# Sheet2.net
KiCad netlist of a schematic drawn in Altium Designer
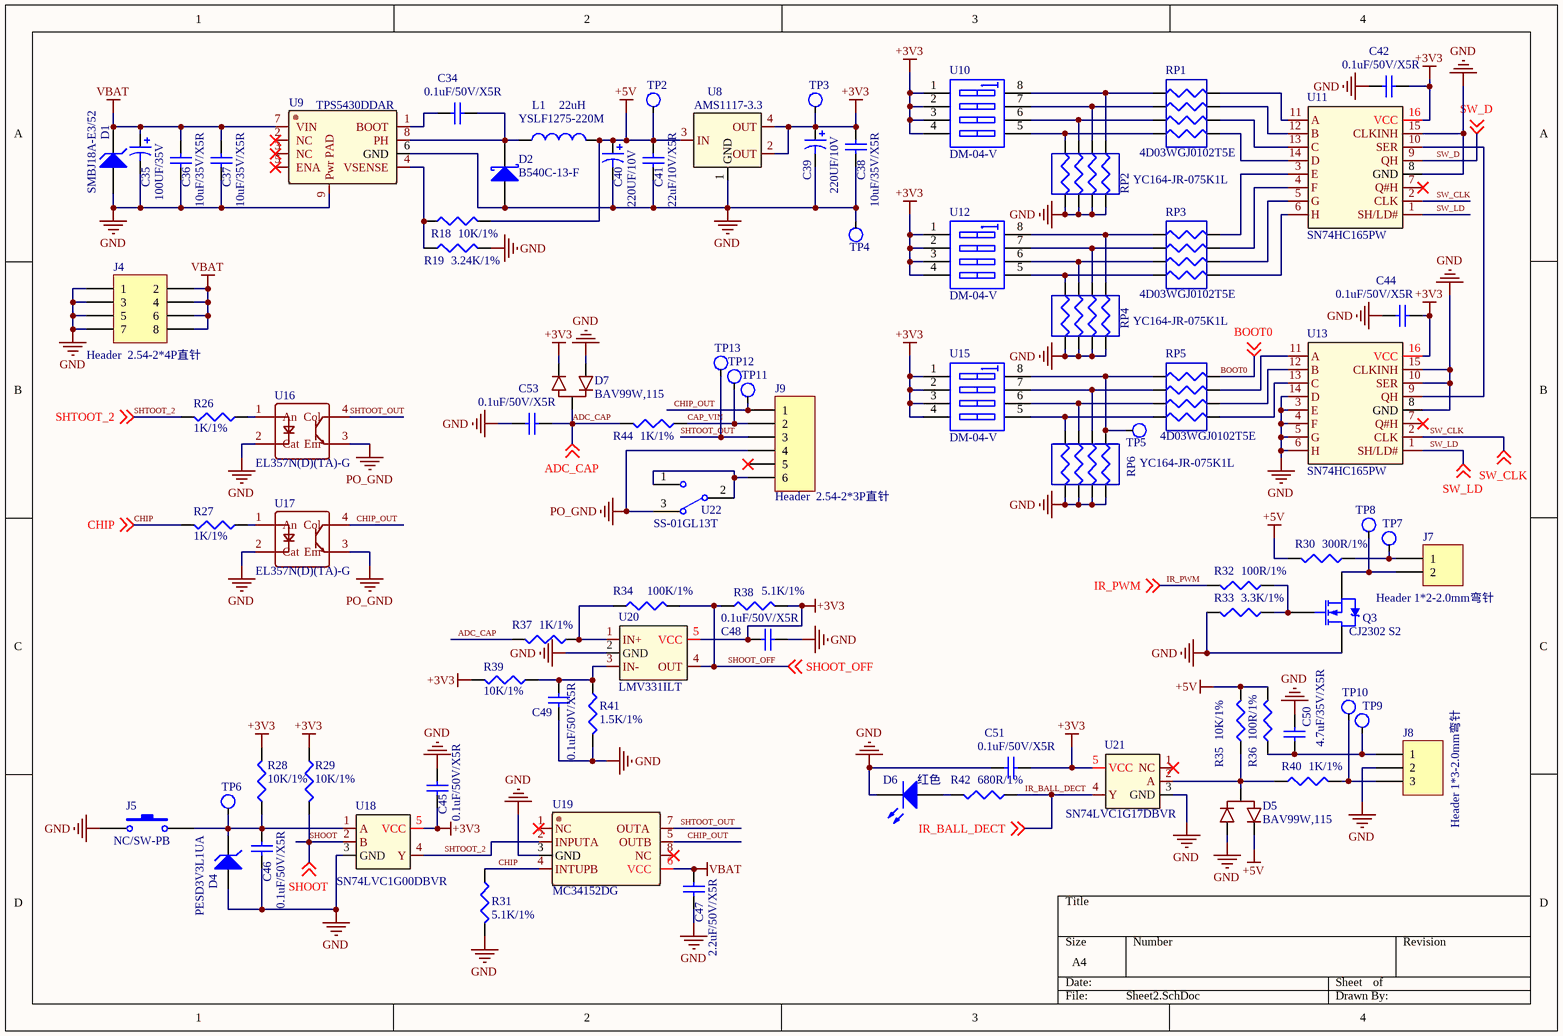
[diagram p0: Sheet2.SchDoc]

(export (version "E")
  (design (tool "Eeschema 10.0.6"))
  (components
    (comp (ref "C34")
      (value "0.1uF/50V/X5R")
      (footprint "C0603")
      (description "Capacitor (Semiconductor SIM Model)")
      (fields (field (name "PUBLISHER") "Altium Limited"))
      (libsource (lib "Miscellaneous Devices") (part "Cap Semi"))
    )
    (comp (ref "C35")
      (value "100UF/35V")
      (footprint "SMD_5X5.4")
      (description "Polarized Capacitor (Radial)")
      (fields (field (name "PUBLISHER") "Altium Limited"))
      (libsource (lib "Miscellaneous Devices") (part "Cap Pol1"))
    )
    (comp (ref "C36")
      (value "10uF/35V/X5R")
      (footprint "C1206")
      (description "Capacitor (Semiconductor SIM Model)")
      (fields (field (name "PUBLISHER") "Altium Limited"))
      (libsource (lib "Miscellaneous Devices") (part "Cap Semi"))
    )
    (comp (ref "C37")
      (value "10uF/35V/X5R")
      (footprint "C1206")
      (description "Capacitor (Semiconductor SIM Model)")
      (fields (field (name "PUBLISHER") "Altium Limited"))
      (libsource (lib "Miscellaneous Devices") (part "Cap Semi"))
    )
    (comp (ref "C38")
      (value "10uF/35V/X5R")
      (footprint "C0805")
      (description "Capacitor (Semiconductor SIM Model)")
      (fields (field (name "PUBLISHER") "Altium Limited"))
      (libsource (lib "Miscellaneous Devices") (part "Cap Semi"))
    )
    (comp (ref "C39")
      (value "220UF/10V")
      (footprint "SMD_5X5.4")
      (description "Polarized Capacitor (Radial)")
      (fields (field (name "PUBLISHER") "Altium Limited"))
      (libsource (lib "Miscellaneous Devices") (part "Cap Pol1"))
    )
    (comp (ref "C40")
      (value "220UF/10V")
      (footprint "SMD_5X5.4")
      (description "Polarized Capacitor (Radial)")
      (fields (field (name "PUBLISHER") "Altium Limited"))
      (libsource (lib "Miscellaneous Devices") (part "Cap Pol1"))
    )
    (comp (ref "C41")
      (value "22uF/10V/X5R")
      (footprint "C0805")
      (description "Capacitor (Semiconductor SIM Model)")
      (fields (field (name "PUBLISHER") "Altium Limited"))
      (libsource (lib "Miscellaneous Devices") (part "Cap Semi"))
    )
    (comp (ref "C42")
      (value "0.1uF/50V/X5R")
      (footprint "C0603")
      (description "Capacitor (Semiconductor SIM Model)")
      (fields (field (name "PUBLISHER") "Altium Limited"))
      (libsource (lib "Miscellaneous Devices") (part "Cap Semi"))
    )
    (comp (ref "C44")
      (value "0.1uF/50V/X5R")
      (footprint "C0603")
      (description "Capacitor (Semiconductor SIM Model)")
      (fields (field (name "PUBLISHER") "Altium Limited"))
      (libsource (lib "Miscellaneous Devices") (part "Cap Semi"))
    )
    (comp (ref "C45")
      (value "0.1uF/50V/X5R")
      (footprint "C0603")
      (description "Capacitor (Semiconductor SIM Model)")
      (fields (field (name "PUBLISHER") "Altium Limited"))
      (libsource (lib "Miscellaneous Devices") (part "Cap Semi"))
    )
    (comp (ref "C46")
      (value "0.1uF/50V/X5R")
      (footprint "C0603")
      (description "Capacitor (Semiconductor SIM Model)")
      (fields (field (name "PUBLISHER") "Altium Limited"))
      (libsource (lib "Miscellaneous Devices") (part "Cap Semi"))
    )
    (comp (ref "C47")
      (value "2.2uF/50V/X5R")
      (footprint "C0603")
      (description "Capacitor (Semiconductor SIM Model)")
      (fields (field (name "PUBLISHER") "Altium Limited"))
      (libsource (lib "Miscellaneous Devices") (part "Cap Semi"))
    )
    (comp (ref "C48")
      (value "0.1uF/50V/X5R")
      (footprint "C0603")
      (description "Capacitor (Semiconductor SIM Model)")
      (fields (field (name "PUBLISHER") "Altium Limited"))
      (libsource (lib "Miscellaneous Devices") (part "Cap Semi"))
    )
    (comp (ref "C49")
      (value "0.1uF/50V/X5R")
      (footprint "C0603")
      (description "Capacitor (Semiconductor SIM Model)")
      (fields (field (name "PUBLISHER") "Altium Limited"))
      (libsource (lib "Miscellaneous Devices") (part "Cap Semi"))
    )
    (comp (ref "C50")
      (value "4.7uF/35V/X5R")
      (footprint "C0603")
      (description "Capacitor (Semiconductor SIM Model)")
      (fields (field (name "PUBLISHER") "Altium Limited"))
      (libsource (lib "Miscellaneous Devices") (part "Cap Semi"))
    )
    (comp (ref "C51")
      (value "0.1uF/50V/X5R")
      (footprint "C0603")
      (description "Capacitor (Semiconductor SIM Model)")
      (fields (field (name "PUBLISHER") "Altium Limited"))
      (libsource (lib "Miscellaneous Devices") (part "Cap Semi"))
    )
    (comp (ref "C53")
      (value "0.1uF/50V/X5R")
      (footprint "C0603")
      (description "Capacitor (Semiconductor SIM Model)")
      (fields (field (name "PUBLISHER") "Altium Limited"))
      (libsource (lib "Miscellaneous Devices") (part "Cap Semi"))
    )
    (comp (ref "D1")
      (value "SMBJ18A-E3/52")
      (footprint "SMB")
      (description "Zener Diode")
      (fields (field (name "PUBLISHER") "Altium Limited"))
      (libsource (lib "Miscellaneous Devices") (part "D Zener"))
    )
    (comp (ref "D2")
      (value "B540C-13-F")
      (footprint "SMC")
      (description "Schottky Diode")
      (fields (field (name "PUBLISHER") "Altium Limited"))
      (libsource (lib "Miscellaneous Devices") (part "D Schottky"))
    )
    (comp (ref "D4")
      (value "PESD3V3L1UA")
      (footprint "SOD-323")
      (libsource (lib "Schlib1") (part "PESD3V3L1UA"))
    )
    (comp (ref "D5") (value "BAV99W,115") (libsource (lib "Schlib1") (part "BAV99W,115")))
    (comp (ref "D6")
      (value "红色")
      (footprint "LED0603")
      (description "Typical RED, GREEN, YELLOW, AMBER GaAs LED")
      (fields (field (name "PUBLISHER") "Altium Limited"))
      (libsource (lib "Miscellaneous Devices") (part "LED2"))
    )
    (comp (ref "D7") (value "BAV99W,115") (libsource (lib "Schlib1") (part "BAV99W,115")))
    (comp (ref "J4")
      (value "Header  2.54-2*4P直针")
      (footprint "DIP_2X4_2.54")
      (description "Header, 4-Pin, Dual row")
      (fields (field (name "PUBLISHER") "Altium Limited"))
      (libsource (lib "Miscellaneous Connectors") (part "Header 4X2"))
    )
    (comp (ref "J5")
      (value "NC/SW-PB")
      (footprint "SMD-AJ")
      (description "Switch")
      (fields (field (name "PUBLISHER") "Altium Limited"))
      (libsource (lib "Miscellaneous Devices") (part "SW-PB"))
    )
    (comp (ref "J7")
      (value "Header 1*2-2.0mm弯针")
      (footprint "DIP_1X2_2MM1")
      (description "Header, 2-Pin")
      (fields (field (name "PUBLISHER") "Altium Limited"))
      (libsource (lib "Miscellaneous Connectors") (part "Header 2"))
    )
    (comp (ref "J8")
      (value "Header 1*3-2.0mm弯针")
      (footprint "DIP_1X3_2MM")
      (description "Header, 3-Pin")
      (fields (field (name "PUBLISHER") "Altium Limited"))
      (libsource (lib "Miscellaneous Connectors") (part "Header 3"))
    )
    (comp (ref "J9")
      (value "Header  2.54-2*3P直针")
      (footprint "DIP_2X3_2.54")
      (description "Header, 6-Pin")
      (fields (field (name "PUBLISHER") "Altium Limited"))
      (libsource (lib "Miscellaneous Connectors") (part "Header 6"))
    )
    (comp (ref "L1")
      (value "YSLF1275-220M")
      (footprint "SMD_12.5X12.")
      (description "Inductor")
      (fields (field (name "ALTIUM_VALUE") "22uH") (field (name "PUBLISHER") "Altium Limited"))
      (libsource (lib "Miscellaneous Devices") (part "Inductor"))
    )
    (comp (ref "Q3")
      (value "CJ2302 S2")
      (footprint "SOT-23")
      (description "N-Channel Power MOSFET")
      (fields (field (name "PUBLISHER") "Altium Limited"))
      (libsource (lib "Miscellaneous Devices") (part "NMOS-2"))
    )
    (comp (ref "R18")
      (value "10K/1%")
      (footprint "R0603")
      (description "Resistor")
      (fields (field (name "PUBLISHER") "Altium Limited"))
      (libsource (lib "Miscellaneous Devices") (part "Res3"))
    )
    (comp (ref "R19")
      (value "3.24K/1%")
      (footprint "R0603")
      (description "Resistor")
      (fields (field (name "PUBLISHER") "Altium Limited"))
      (libsource (lib "Miscellaneous Devices") (part "Res3"))
    )
    (comp (ref "R26")
      (value "1K/1%")
      (footprint "R0603")
      (description "Resistor")
      (fields (field (name "PUBLISHER") "Altium Limited"))
      (libsource (lib "Miscellaneous Devices") (part "Res3"))
    )
    (comp (ref "R27")
      (value "1K/1%")
      (footprint "R0603")
      (description "Resistor")
      (fields (field (name "PUBLISHER") "Altium Limited"))
      (libsource (lib "Miscellaneous Devices") (part "Res3"))
    )
    (comp (ref "R28")
      (value "10K/1%")
      (footprint "R0603")
      (description "Resistor")
      (fields (field (name "PUBLISHER") "Altium Limited"))
      (libsource (lib "Miscellaneous Devices") (part "Res3"))
    )
    (comp (ref "R29")
      (value "10K/1%")
      (footprint "R0603")
      (description "Resistor")
      (fields (field (name "PUBLISHER") "Altium Limited"))
      (libsource (lib "Miscellaneous Devices") (part "Res3"))
    )
    (comp (ref "R30")
      (value "300R/1%")
      (footprint "R0603")
      (description "Resistor")
      (fields (field (name "PUBLISHER") "Altium Limited"))
      (libsource (lib "Miscellaneous Devices") (part "Res3"))
    )
    (comp (ref "R31")
      (value "5.1K/1%")
      (footprint "R0603")
      (description "Resistor")
      (fields (field (name "PUBLISHER") "Altium Limited"))
      (libsource (lib "Miscellaneous Devices") (part "Res3"))
    )
    (comp (ref "R32")
      (value "100R/1%")
      (footprint "R0603")
      (description "Resistor")
      (fields (field (name "PUBLISHER") "Altium Limited"))
      (libsource (lib "Miscellaneous Devices") (part "Res3"))
    )
    (comp (ref "R33")
      (value "3.3K/1%")
      (footprint "R0603")
      (description "Resistor")
      (fields (field (name "PUBLISHER") "Altium Limited"))
      (libsource (lib "Miscellaneous Devices") (part "Res3"))
    )
    (comp (ref "R34")
      (value "100K/1%")
      (footprint "R0603")
      (description "Resistor")
      (fields (field (name "PUBLISHER") "Altium Limited"))
      (libsource (lib "Miscellaneous Devices") (part "Res3"))
    )
    (comp (ref "R35")
      (value "10K/1%")
      (footprint "R0603")
      (description "Resistor")
      (fields (field (name "PUBLISHER") "Altium Limited"))
      (libsource (lib "Miscellaneous Devices") (part "Res3"))
    )
    (comp (ref "R36")
      (value "100R/1%")
      (footprint "R0603")
      (description "Resistor")
      (fields (field (name "PUBLISHER") "Altium Limited"))
      (libsource (lib "Miscellaneous Devices") (part "Res3"))
    )
    (comp (ref "R37")
      (value "1K/1%")
      (footprint "R0603")
      (description "Resistor")
      (fields (field (name "PUBLISHER") "Altium Limited"))
      (libsource (lib "Miscellaneous Devices") (part "Res3"))
    )
    (comp (ref "R38")
      (value "5.1K/1%")
      (footprint "R0603")
      (description "Resistor")
      (fields (field (name "PUBLISHER") "Altium Limited"))
      (libsource (lib "Miscellaneous Devices") (part "Res3"))
    )
    (comp (ref "R39")
      (value "10K/1%")
      (footprint "R0603")
      (description "Resistor")
      (fields (field (name "PUBLISHER") "Altium Limited"))
      (libsource (lib "Miscellaneous Devices") (part "Res3"))
    )
    (comp (ref "R40")
      (value "1K/1%")
      (footprint "R0603")
      (description "Resistor")
      (fields (field (name "PUBLISHER") "Altium Limited"))
      (libsource (lib "Miscellaneous Devices") (part "Res3"))
    )
    (comp (ref "R41")
      (value "1.5K/1%")
      (footprint "R0603")
      (description "Resistor")
      (fields (field (name "PUBLISHER") "Altium Limited"))
      (libsource (lib "Miscellaneous Devices") (part "Res3"))
    )
    (comp (ref "R42")
      (value "680R/1%")
      (footprint "R0603")
      (description "Resistor")
      (fields (field (name "PUBLISHER") "Altium Limited"))
      (libsource (lib "Miscellaneous Devices") (part "Res3"))
    )
    (comp (ref "R44")
      (value "1K/1%")
      (footprint "R0603")
      (description "Resistor")
      (fields (field (name "PUBLISHER") "Altium Limited"))
      (libsource (lib "Miscellaneous Devices") (part "Res3"))
    )
    (comp (ref "RP1") (value "4D03WGJ0102T5E") (footprint "RP-1206") (libsource (lib "Schlib1") (part "RP")))
    (comp (ref "RP2") (value "YC164-JR-075K1L") (footprint "RP-1206") (libsource (lib "Schlib1") (part "RP")))
    (comp (ref "RP3") (value "4D03WGJ0102T5E") (footprint "RP-1206") (libsource (lib "Schlib1") (part "RP")))
    (comp (ref "RP4") (value "YC164-JR-075K1L") (footprint "RP-1206") (libsource (lib "Schlib1") (part "RP")))
    (comp (ref "RP5") (value "4D03WGJ0102T5E") (footprint "RP-1206") (libsource (lib "Schlib1") (part "RP")))
    (comp (ref "RP6") (value "YC164-JR-075K1L") (footprint "RP-1206") (libsource (lib "Schlib1") (part "RP")))
    (comp (ref "TP2") (value "TP") (footprint "TP") (libsource (lib "Schlib1") (part "TP")))
    (comp (ref "TP3") (value "TP") (footprint "TP") (libsource (lib "Schlib1") (part "TP")))
    (comp (ref "TP4") (value "TP") (footprint "TP") (libsource (lib "Schlib1") (part "TP")))
    (comp (ref "TP5") (value "TP") (footprint "TP") (libsource (lib "Schlib1") (part "TP")))
    (comp (ref "TP6") (value "TP") (footprint "TP") (libsource (lib "Schlib1") (part "TP")))
    (comp (ref "TP7") (value "TP") (footprint "TP") (libsource (lib "Schlib1") (part "TP")))
    (comp (ref "TP8") (value "TP") (footprint "TP") (libsource (lib "Schlib1") (part "TP")))
    (comp (ref "TP9") (value "TP") (footprint "TP") (libsource (lib "Schlib1") (part "TP")))
    (comp (ref "TP10") (value "TP") (footprint "TP") (libsource (lib "Schlib1") (part "TP")))
    (comp (ref "TP11") (value "TP") (footprint "TP") (libsource (lib "Schlib1") (part "TP")))
    (comp (ref "TP12") (value "TP") (footprint "TP") (libsource (lib "Schlib1") (part "TP")))
    (comp (ref "TP13") (value "TP") (footprint "TP") (libsource (lib "Schlib1") (part "TP")))
    (comp (ref "U8")
      (value "AMS1117-3.3")
      (footprint "SOT-223")
      (libsource (lib "Schlib1") (part "AMS1117-3.3"))
    )
    (comp (ref "U9")
      (value "TPS5430DDAR")
      (footprint "SO-8")
      (libsource (lib "Schlib1") (part "TPS5430DDAR"))
    )
    (comp (ref "U10")
      (value "DM-04-V")
      (footprint "SMD_DM04")
      (description "DIP Switch, 4 Position, SPST")
      (fields (field (name "PUBLISHER") "Altium Limited"))
      (libsource (lib "Miscellaneous Devices") (part "SW DIP-4"))
    )
    (comp (ref "U11")
      (value "SN74HC165PW")
      (footprint "TSSOP-16")
      (libsource (lib "Schlib1") (part "SN74HC165PW"))
    )
    (comp (ref "U12")
      (value "DM-04-V")
      (footprint "SMD_DM04")
      (description "DIP Switch, 4 Position, SPST")
      (fields (field (name "PUBLISHER") "Altium Limited"))
      (libsource (lib "Miscellaneous Devices") (part "SW DIP-4"))
    )
    (comp (ref "U13")
      (value "SN74HC165PW")
      (footprint "TSSOP-16")
      (libsource (lib "Schlib1") (part "SN74HC165PW"))
    )
    (comp (ref "U15")
      (value "DM-04-V")
      (footprint "SMD_DM04")
      (description "DIP Switch, 4 Position, SPST")
      (fields (field (name "PUBLISHER") "Altium Limited"))
      (libsource (lib "Miscellaneous Devices") (part "SW DIP-4"))
    )
    (comp (ref "U16")
      (value "EL357N(D)(TA)-G")
      (footprint "SOP-4_P2.54")
      (libsource (lib "Schlib1") (part "EL357N(D)(TA)-G"))
    )
    (comp (ref "U17")
      (value "EL357N(D)(TA)-G")
      (footprint "SOP-4_P2.54")
      (libsource (lib "Schlib1") (part "EL357N(D)(TA)-G"))
    )
    (comp (ref "U18")
      (value "SN74LVC1G00DBVR")
      (footprint "SOT-23-5")
      (libsource (lib "Schlib1") (part "SN74LVC1G00DBVR"))
    )
    (comp (ref "U19") (value "MC34152DG") (footprint "SOIC-8") (libsource (lib "Schlib1") (part "MC34152DG")))
    (comp (ref "U20")
      (value "LMV331ILT")
      (footprint "SOT-23-5")
      (libsource (lib "Schlib1") (part "LMV331IDBVR"))
    )
    (comp (ref "U21")
      (value "SN74LVC1G17DBVR")
      (footprint "SOT-23-5")
      (libsource (lib "Schlib1") (part "SN74LVC1G17DBVR"))
    )
    (comp (ref "U22")
      (value "SS-01GL13T")
      (footprint "SW-6.4X19.8")
      (description "SPDT Subminiature Toggle Switch, Right Angle Mounting, Vertical Actuation")
      (fields (field (name "PUBLISHER") "Altium Limited"))
      (libsource (lib "Miscellaneous Devices") (part "SW-SPDT"))
    )
  )
  (nets
    (net (code "1") (name "+3V3") (class "Default")
      (node (ref "C38") (pin "1") (pinfunction "1_1") (pintype "passive"))
      (node (ref "C39") (pin "1") (pinfunction "1_1") (pintype "passive"))
      (node (ref "C42") (pin "1") (pinfunction "1_1") (pintype "passive"))
      (node (ref "C44") (pin "1") (pinfunction "1_1") (pintype "passive"))
      (node (ref "C45") (pin "1") (pinfunction "1_1") (pintype "passive"))
      (node (ref "C48") (pin "2") (pinfunction "2_2") (pintype "passive"))
      (node (ref "C51") (pin "1") (pinfunction "1_1") (pintype "passive"))
      (node (ref "D7") (pin "2") (pinfunction "2_2") (pintype "passive"))
      (node (ref "R28") (pin "2") (pinfunction "2_2") (pintype "passive"))
      (node (ref "R29") (pin "1") (pinfunction "1_1") (pintype "passive"))
      (node (ref "R38") (pin "2") (pinfunction "2_2") (pintype "passive"))
      (node (ref "R39") (pin "2") (pinfunction "2_2") (pintype "passive"))
      (node (ref "TP3") (pin "1") (pinfunction "1_1") (pintype "passive"))
      (node (ref "U10") (pin "1") (pinfunction "A1_1") (pintype "passive"))
      (node (ref "U10") (pin "2") (pinfunction "A2_2") (pintype "passive"))
      (node (ref "U10") (pin "3") (pinfunction "A3_3") (pintype "passive"))
      (node (ref "U10") (pin "4") (pinfunction "A4_4") (pintype "passive"))
      (node (ref "U11") (pin "16") (pinfunction "VCC_16") (pintype "passive"))
      (node (ref "U12") (pin "1") (pinfunction "A1_1") (pintype "passive"))
      (node (ref "U12") (pin "2") (pinfunction "A2_2") (pintype "passive"))
      (node (ref "U12") (pin "3") (pinfunction "A3_3") (pintype "passive"))
      (node (ref "U12") (pin "4") (pinfunction "A4_4") (pintype "passive"))
      (node (ref "U13") (pin "16") (pinfunction "VCC_16") (pintype "passive"))
      (node (ref "U15") (pin "1") (pinfunction "A1_1") (pintype "passive"))
      (node (ref "U15") (pin "2") (pinfunction "A2_2") (pintype "passive"))
      (node (ref "U15") (pin "3") (pinfunction "A3_3") (pintype "passive"))
      (node (ref "U15") (pin "4") (pinfunction "A4_4") (pintype "passive"))
      (node (ref "U18") (pin "5") (pinfunction "VCC_5") (pintype "passive"))
      (node (ref "U20") (pin "5") (pinfunction "VCC_5") (pintype "passive"))
      (node (ref "U21") (pin "5") (pinfunction "VCC_5") (pintype "passive"))
      (node (ref "U8") (pin "2") (pinfunction "OUT_2") (pintype "passive"))
      (node (ref "U8") (pin "4") (pinfunction "OUT_4") (pintype "passive"))
    )
    (net (code "2") (name "+5V") (class "Default")
      (node (ref "C40") (pin "1") (pinfunction "1_1") (pintype "passive"))
      (node (ref "C41") (pin "1") (pinfunction "1_1") (pintype "passive"))
      (node (ref "D5") (pin "2") (pinfunction "2_2") (pintype "passive"))
      (node (ref "L1") (pin "1") (pinfunction "1_1") (pintype "passive"))
      (node (ref "R18") (pin "2") (pinfunction "2_2") (pintype "passive"))
      (node (ref "R30") (pin "2") (pinfunction "2_2") (pintype "passive"))
      (node (ref "R35") (pin "2") (pinfunction "2_2") (pintype "passive"))
      (node (ref "R36") (pin "2") (pinfunction "2_2") (pintype "passive"))
      (node (ref "TP2") (pin "1") (pinfunction "1_1") (pintype "passive"))
      (node (ref "U8") (pin "3") (pinfunction "IN_3") (pintype "passive"))
    )
    (net (code "3") (name "/CAP_VIN") (class "Default")
      (node (ref "J9") (pin "2") (pinfunction "2_2") (pintype "passive"))
      (node (ref "R44") (pin "1") (pinfunction "1_1") (pintype "passive"))
      (node (ref "TP12") (pin "1") (pinfunction "1_1") (pintype "passive"))
    )
    (net (code "4") (name "/CHIP_OUT") (class "Default")
      (node (ref "J9") (pin "1") (pinfunction "1_1") (pintype "passive"))
      (node (ref "TP11") (pin "1") (pinfunction "1_1") (pintype "passive"))
      (node (ref "U17") (pin "4") (pinfunction "Col_4") (pintype "passive"))
      (node (ref "U19") (pin "5") (pinfunction "OUTB_5") (pintype "passive"))
    )
    (net (code "5") (name "/SHTOOT_OUT") (class "Default")
      (node (ref "J9") (pin "3") (pinfunction "3_3") (pintype "passive"))
      (node (ref "TP13") (pin "1") (pinfunction "1_1") (pintype "passive"))
      (node (ref "U16") (pin "4") (pinfunction "Col_4") (pintype "passive"))
      (node (ref "U19") (pin "7") (pinfunction "OUTA_7") (pintype "passive"))
    )
    (net (code "6") (name "ADC_CAP") (class "Default")
      (node (ref "C53") (pin "1") (pinfunction "1_1") (pintype "passive"))
      (node (ref "D7") (pin "3") (pinfunction "3_3") (pintype "passive"))
      (node (ref "R37") (pin "2") (pinfunction "2_2") (pintype "passive"))
      (node (ref "R44") (pin "2") (pinfunction "2_2") (pintype "passive"))
    )
    (net (code "7") (name "BOOT0") (class "Default")
      (node (ref "RP5") (pin "1") (pinfunction "1_1") (pintype "passive"))
    )
    (net (code "8") (name "CHIP") (class "Default")
      (node (ref "R27") (pin "2") (pinfunction "2_2") (pintype "passive"))
      (node (ref "R31") (pin "1") (pinfunction "1_1") (pintype "passive"))
      (node (ref "U19") (pin "4") (pinfunction "INTUPB_4") (pintype "passive"))
    )
    (net (code "9") (name "GND") (class "Default")
      (node (ref "C35") (pin "2") (pinfunction "2_2") (pintype "passive"))
      (node (ref "C36") (pin "2") (pinfunction "2_2") (pintype "passive"))
      (node (ref "C37") (pin "2") (pinfunction "2_2") (pintype "passive"))
      (node (ref "C38") (pin "2") (pinfunction "2_2") (pintype "passive"))
      (node (ref "C39") (pin "2") (pinfunction "2_2") (pintype "passive"))
      (node (ref "C40") (pin "2") (pinfunction "2_2") (pintype "passive"))
      (node (ref "C41") (pin "2") (pinfunction "2_2") (pintype "passive"))
      (node (ref "C42") (pin "2") (pinfunction "2_2") (pintype "passive"))
      (node (ref "C44") (pin "2") (pinfunction "2_2") (pintype "passive"))
      (node (ref "C45") (pin "2") (pinfunction "2_2") (pintype "passive"))
      (node (ref "C46") (pin "2") (pinfunction "2_2") (pintype "passive"))
      (node (ref "C47") (pin "2") (pinfunction "2_2") (pintype "passive"))
      (node (ref "C48") (pin "1") (pinfunction "1_1") (pintype "passive"))
      (node (ref "C49") (pin "2") (pinfunction "2_2") (pintype "passive"))
      (node (ref "C50") (pin "2") (pinfunction "2_2") (pintype "passive"))
      (node (ref "C51") (pin "2") (pinfunction "2_2") (pintype "passive"))
      (node (ref "C53") (pin "2") (pinfunction "2_2") (pintype "passive"))
      (node (ref "D1") (pin "1") (pinfunction "A_1") (pintype "passive"))
      (node (ref "D2") (pin "1") (pinfunction "A_1") (pintype "passive"))
      (node (ref "D4") (pin "2") (pinfunction "A_2") (pintype "passive"))
      (node (ref "D5") (pin "1") (pinfunction "1_1") (pintype "passive"))
      (node (ref "D6") (pin "2") (pinfunction "K_2") (pintype "passive"))
      (node (ref "D7") (pin "1") (pinfunction "1_1") (pintype "passive"))
      (node (ref "J4") (pin "1") (pinfunction "1_1") (pintype "passive"))
      (node (ref "J4") (pin "3") (pinfunction "3_3") (pintype "passive"))
      (node (ref "J4") (pin "5") (pinfunction "5_5") (pintype "passive"))
      (node (ref "J4") (pin "7") (pinfunction "7_7") (pintype "passive"))
      (node (ref "J5") (pin "2") (pinfunction "2_2") (pintype "passive"))
      (node (ref "J8") (pin "2") (pinfunction "2_2") (pintype "passive"))
      (node (ref "Q3") (pin "2") (pinfunction "D_2") (pintype "passive"))
      (node (ref "R19") (pin "2") (pinfunction "2_2") (pintype "passive"))
      (node (ref "R31") (pin "2") (pinfunction "2_2") (pintype "passive"))
      (node (ref "R33") (pin "2") (pinfunction "2_2") (pintype "passive"))
      (node (ref "R41") (pin "2") (pinfunction "2_2") (pintype "passive"))
      (node (ref "RP2") (pin "5") (pinfunction "5_5") (pintype "passive"))
      (node (ref "RP2") (pin "6") (pinfunction "6_6") (pintype "passive"))
      (node (ref "RP2") (pin "7") (pinfunction "7_7") (pintype "passive"))
      (node (ref "RP2") (pin "8") (pinfunction "8_8") (pintype "passive"))
      (node (ref "RP4") (pin "5") (pinfunction "5_5") (pintype "passive"))
      (node (ref "RP4") (pin "6") (pinfunction "6_6") (pintype "passive"))
      (node (ref "RP4") (pin "7") (pinfunction "7_7") (pintype "passive"))
      (node (ref "RP4") (pin "8") (pinfunction "8_8") (pintype "passive"))
      (node (ref "RP6") (pin "5") (pinfunction "5_5") (pintype "passive"))
      (node (ref "RP6") (pin "6") (pinfunction "6_6") (pintype "passive"))
      (node (ref "RP6") (pin "7") (pinfunction "7_7") (pintype "passive"))
      (node (ref "RP6") (pin "8") (pinfunction "8_8") (pintype "passive"))
      (node (ref "TP4") (pin "1") (pinfunction "1_1") (pintype "passive"))
      (node (ref "U11") (pin "15") (pinfunction "CLKINH_15") (pintype "passive"))
      (node (ref "U11") (pin "8") (pinfunction "GND_8") (pintype "passive"))
      (node (ref "U13") (pin "10") (pinfunction "SER_10") (pintype "passive"))
      (node (ref "U13") (pin "14") (pinfunction "D_14") (pintype "passive"))
      (node (ref "U13") (pin "15") (pinfunction "CLKINH_15") (pintype "passive"))
      (node (ref "U13") (pin "3") (pinfunction "E_3") (pintype "passive"))
      (node (ref "U13") (pin "4") (pinfunction "F_4") (pintype "passive"))
      (node (ref "U13") (pin "5") (pinfunction "G_5") (pintype "passive"))
      (node (ref "U13") (pin "6") (pinfunction "H_6") (pintype "passive"))
      (node (ref "U13") (pin "8") (pinfunction "GND_8") (pintype "passive"))
      (node (ref "U16") (pin "2") (pinfunction "Cat_2") (pintype "passive"))
      (node (ref "U17") (pin "2") (pinfunction "Cat_2") (pintype "passive"))
      (node (ref "U18") (pin "3") (pinfunction "GND_3") (pintype "passive"))
      (node (ref "U19") (pin "3") (pinfunction "GND_3") (pintype "passive"))
      (node (ref "U20") (pin "2") (pinfunction "GND_2") (pintype "passive"))
      (node (ref "U21") (pin "3") (pinfunction "GND_3") (pintype "passive"))
      (node (ref "U8") (pin "1") (pinfunction "GND_1") (pintype "passive"))
      (node (ref "U9") (pin "6") (pinfunction "GND_6") (pintype "passive"))
      (node (ref "U9") (pin "9") (pinfunction "Pwr_PAD_9") (pintype "passive"))
    )
    (net (code "10") (name "IR_BALL_DECT") (class "Default")
      (node (ref "R42") (pin "1") (pinfunction "1_1") (pintype "passive"))
      (node (ref "U21") (pin "4") (pinfunction "Y_4") (pintype "passive"))
    )
    (net (code "11") (name "IR_PWM") (class "Default")
      (node (ref "R32") (pin "2") (pinfunction "2_2") (pintype "passive"))
    )
    (net (code "12") (name "Net-(C50-Pad1)") (class "Default")
      (node (ref "C50") (pin "1") (pinfunction "1_1") (pintype "passive"))
      (node (ref "J8") (pin "1") (pinfunction "1_1") (pintype "passive"))
      (node (ref "R36") (pin "1") (pinfunction "1_1") (pintype "passive"))
      (node (ref "TP9") (pin "1") (pinfunction "1_1") (pintype "passive"))
    )
    (net (code "13") (name "Net-(D2-K)") (class "Default")
      (node (ref "C34") (pin "2") (pinfunction "2_2") (pintype "passive"))
      (node (ref "D2") (pin "2") (pinfunction "K_2") (pintype "passive"))
      (node (ref "L1") (pin "2") (pinfunction "2_2") (pintype "passive"))
      (node (ref "U9") (pin "8") (pinfunction "PH_8") (pintype "passive"))
    )
    (net (code "14") (name "Net-(D4-K)") (class "Default")
      (node (ref "C46") (pin "1") (pinfunction "1_1") (pintype "passive"))
      (node (ref "D4") (pin "1") (pinfunction "K_1") (pintype "passive"))
      (node (ref "J5") (pin "1") (pinfunction "1_1") (pintype "passive"))
      (node (ref "R28") (pin "1") (pinfunction "1_1") (pintype "passive"))
      (node (ref "TP6") (pin "1") (pinfunction "1_1") (pintype "passive"))
      (node (ref "U18") (pin "1") (pinfunction "A_1") (pintype "passive"))
    )
    (net (code "15") (name "Net-(D6-A)") (class "Default")
      (node (ref "D6") (pin "1") (pinfunction "A_1") (pintype "passive"))
      (node (ref "R42") (pin "2") (pinfunction "2_2") (pintype "passive"))
    )
    (net (code "16") (name "Net-(J7-Pad1)") (class "Default")
      (node (ref "J7") (pin "1") (pinfunction "1_1") (pintype "passive"))
      (node (ref "R30") (pin "1") (pinfunction "1_1") (pintype "passive"))
      (node (ref "TP7") (pin "1") (pinfunction "1_1") (pintype "passive"))
    )
    (net (code "17") (name "Net-(J8-Pad3)") (class "Default")
      (node (ref "J8") (pin "3") (pinfunction "3_3") (pintype "passive"))
      (node (ref "R40") (pin "2") (pinfunction "2_2") (pintype "passive"))
      (node (ref "TP10") (pin "1") (pinfunction "1_1") (pintype "passive"))
    )
    (net (code "18") (name "Net-(J9-Pad6)") (class "Default")
      (node (ref "J9") (pin "6") (pinfunction "6_6") (pintype "passive"))
      (node (ref "U22") (pin "1") (pinfunction "1_1") (pintype "passive"))
      (node (ref "U22") (pin "2") (pinfunction "2_2") (pintype "passive"))
    )
    (net (code "19") (name "Net-(Q3-G)") (class "Default")
      (node (ref "Q3") (pin "1") (pinfunction "G_1") (pintype "passive"))
      (node (ref "R32") (pin "1") (pinfunction "1_1") (pintype "passive"))
      (node (ref "R33") (pin "1") (pinfunction "1_1") (pintype "passive"))
    )
    (net (code "20") (name "Net-(Q3-S)") (class "Default")
      (node (ref "J7") (pin "2") (pinfunction "2_2") (pintype "passive"))
      (node (ref "Q3") (pin "3") (pinfunction "S_3") (pintype "passive"))
      (node (ref "TP8") (pin "1") (pinfunction "1_1") (pintype "passive"))
    )
    (net (code "21") (name "Net-(U9-BOOT)") (class "Default")
      (node (ref "C34") (pin "1") (pinfunction "1_1") (pintype "passive"))
      (node (ref "U9") (pin "1") (pinfunction "BOOT_1") (pintype "passive"))
    )
    (net (code "22") (name "Net-(U9-VSENSE)") (class "Default")
      (node (ref "R18") (pin "1") (pinfunction "1_1") (pintype "passive"))
      (node (ref "R19") (pin "1") (pinfunction "1_1") (pintype "passive"))
      (node (ref "U9") (pin "4") (pinfunction "VSENSE_4") (pintype "passive"))
    )
    (net (code "23") (name "Net-(U10-B1)") (class "Default")
      (node (ref "RP1") (pin "8") (pinfunction "8_8") (pintype "passive"))
      (node (ref "RP2") (pin "1") (pinfunction "1_1") (pintype "passive"))
      (node (ref "U10") (pin "8") (pinfunction "B1_8") (pintype "passive"))
    )
    (net (code "24") (name "Net-(U10-B2)") (class "Default")
      (node (ref "RP1") (pin "7") (pinfunction "7_7") (pintype "passive"))
      (node (ref "RP2") (pin "2") (pinfunction "2_2") (pintype "passive"))
      (node (ref "U10") (pin "7") (pinfunction "B2_7") (pintype "passive"))
    )
    (net (code "25") (name "Net-(U10-B3)") (class "Default")
      (node (ref "RP1") (pin "6") (pinfunction "6_6") (pintype "passive"))
      (node (ref "RP2") (pin "3") (pinfunction "3_3") (pintype "passive"))
      (node (ref "U10") (pin "6") (pinfunction "B3_6") (pintype "passive"))
    )
    (net (code "26") (name "Net-(U10-B4)") (class "Default")
      (node (ref "RP1") (pin "5") (pinfunction "5_5") (pintype "passive"))
      (node (ref "RP2") (pin "4") (pinfunction "4_4") (pintype "passive"))
      (node (ref "U10") (pin "5") (pinfunction "B4_5") (pintype "passive"))
    )
    (net (code "27") (name "Net-(U11-A)") (class "Default")
      (node (ref "RP1") (pin "1") (pinfunction "1_1") (pintype "passive"))
      (node (ref "U11") (pin "11") (pinfunction "A_11") (pintype "passive"))
    )
    (net (code "28") (name "Net-(U11-B)") (class "Default")
      (node (ref "RP1") (pin "2") (pinfunction "2_2") (pintype "passive"))
      (node (ref "U11") (pin "12") (pinfunction "B_12") (pintype "passive"))
    )
    (net (code "29") (name "Net-(U11-C)") (class "Default")
      (node (ref "RP1") (pin "3") (pinfunction "3_3") (pintype "passive"))
      (node (ref "U11") (pin "13") (pinfunction "C_13") (pintype "passive"))
    )
    (net (code "30") (name "Net-(U11-D)") (class "Default")
      (node (ref "RP1") (pin "4") (pinfunction "4_4") (pintype "passive"))
      (node (ref "U11") (pin "14") (pinfunction "D_14") (pintype "passive"))
    )
    (net (code "31") (name "Net-(U11-E)") (class "Default")
      (node (ref "RP3") (pin "1") (pinfunction "1_1") (pintype "passive"))
      (node (ref "U11") (pin "3") (pinfunction "E_3") (pintype "passive"))
    )
    (net (code "32") (name "Net-(U11-F)") (class "Default")
      (node (ref "RP3") (pin "2") (pinfunction "2_2") (pintype "passive"))
      (node (ref "U11") (pin "4") (pinfunction "F_4") (pintype "passive"))
    )
    (net (code "33") (name "Net-(U11-G)") (class "Default")
      (node (ref "RP3") (pin "3") (pinfunction "3_3") (pintype "passive"))
      (node (ref "U11") (pin "5") (pinfunction "G_5") (pintype "passive"))
    )
    (net (code "34") (name "Net-(U11-H)") (class "Default")
      (node (ref "RP3") (pin "4") (pinfunction "4_4") (pintype "passive"))
      (node (ref "U11") (pin "6") (pinfunction "H_6") (pintype "passive"))
    )
    (net (code "35") (name "Net-(U11-SER)") (class "Default")
      (node (ref "U11") (pin "10") (pinfunction "SER_10") (pintype "passive"))
      (node (ref "U13") (pin "9") (pinfunction "QH_9") (pintype "passive"))
    )
    (net (code "36") (name "Net-(U12-B1)") (class "Default")
      (node (ref "RP3") (pin "8") (pinfunction "8_8") (pintype "passive"))
      (node (ref "RP4") (pin "1") (pinfunction "1_1") (pintype "passive"))
      (node (ref "U12") (pin "8") (pinfunction "B1_8") (pintype "passive"))
    )
    (net (code "37") (name "Net-(U12-B2)") (class "Default")
      (node (ref "RP3") (pin "7") (pinfunction "7_7") (pintype "passive"))
      (node (ref "RP4") (pin "2") (pinfunction "2_2") (pintype "passive"))
      (node (ref "U12") (pin "7") (pinfunction "B2_7") (pintype "passive"))
    )
    (net (code "38") (name "Net-(U12-B3)") (class "Default")
      (node (ref "RP3") (pin "6") (pinfunction "6_6") (pintype "passive"))
      (node (ref "RP4") (pin "3") (pinfunction "3_3") (pintype "passive"))
      (node (ref "U12") (pin "6") (pinfunction "B3_6") (pintype "passive"))
    )
    (net (code "39") (name "Net-(U12-B4)") (class "Default")
      (node (ref "RP3") (pin "5") (pinfunction "5_5") (pintype "passive"))
      (node (ref "RP4") (pin "4") (pinfunction "4_4") (pintype "passive"))
      (node (ref "U12") (pin "5") (pinfunction "B4_5") (pintype "passive"))
    )
    (net (code "40") (name "Net-(U13-A)") (class "Default")
      (node (ref "RP5") (pin "2") (pinfunction "2_2") (pintype "passive"))
      (node (ref "U13") (pin "11") (pinfunction "A_11") (pintype "passive"))
    )
    (net (code "41") (name "Net-(U13-B)") (class "Default")
      (node (ref "RP5") (pin "3") (pinfunction "3_3") (pintype "passive"))
      (node (ref "U13") (pin "12") (pinfunction "B_12") (pintype "passive"))
    )
    (net (code "42") (name "Net-(U13-C)") (class "Default")
      (node (ref "RP5") (pin "4") (pinfunction "4_4") (pintype "passive"))
      (node (ref "U13") (pin "13") (pinfunction "C_13") (pintype "passive"))
    )
    (net (code "43") (name "Net-(U15-B1)") (class "Default")
      (node (ref "RP5") (pin "8") (pinfunction "8_8") (pintype "passive"))
      (node (ref "RP6") (pin "1") (pinfunction "1_1") (pintype "passive"))
      (node (ref "TP5") (pin "1") (pinfunction "1_1") (pintype "passive"))
      (node (ref "U15") (pin "8") (pinfunction "B1_8") (pintype "passive"))
    )
    (net (code "44") (name "Net-(U15-B2)") (class "Default")
      (node (ref "RP5") (pin "7") (pinfunction "7_7") (pintype "passive"))
      (node (ref "RP6") (pin "2") (pinfunction "2_2") (pintype "passive"))
      (node (ref "U15") (pin "7") (pinfunction "B2_7") (pintype "passive"))
    )
    (net (code "45") (name "Net-(U15-B3)") (class "Default")
      (node (ref "RP5") (pin "6") (pinfunction "6_6") (pintype "passive"))
      (node (ref "RP6") (pin "3") (pinfunction "3_3") (pintype "passive"))
      (node (ref "U15") (pin "6") (pinfunction "B3_6") (pintype "passive"))
    )
    (net (code "46") (name "Net-(U15-B4)") (class "Default")
      (node (ref "RP5") (pin "5") (pinfunction "5_5") (pintype "passive"))
      (node (ref "RP6") (pin "4") (pinfunction "4_4") (pintype "passive"))
      (node (ref "U15") (pin "5") (pinfunction "B4_5") (pintype "passive"))
    )
    (net (code "47") (name "Net-(U16-An)") (class "Default")
      (node (ref "R26") (pin "1") (pinfunction "1_1") (pintype "passive"))
      (node (ref "U16") (pin "1") (pinfunction "An_1") (pintype "passive"))
    )
    (net (code "48") (name "Net-(U17-An)") (class "Default")
      (node (ref "R27") (pin "1") (pinfunction "1_1") (pintype "passive"))
      (node (ref "U17") (pin "1") (pinfunction "An_1") (pintype "passive"))
    )
    (net (code "49") (name "Net-(U20-IN+)") (class "Default")
      (node (ref "R34") (pin "1") (pinfunction "1_1") (pintype "passive"))
      (node (ref "R37") (pin "1") (pinfunction "1_1") (pintype "passive"))
      (node (ref "U20") (pin "1") (pinfunction "IN+_1") (pintype "passive"))
    )
    (net (code "50") (name "Net-(U20-IN-)") (class "Default")
      (node (ref "C49") (pin "1") (pinfunction "1_1") (pintype "passive"))
      (node (ref "R39") (pin "1") (pinfunction "1_1") (pintype "passive"))
      (node (ref "R41") (pin "1") (pinfunction "1_1") (pintype "passive"))
      (node (ref "U20") (pin "3") (pinfunction "IN-_3") (pintype "passive"))
    )
    (net (code "51") (name "Net-(U21-A)") (class "Default")
      (node (ref "D5") (pin "3") (pinfunction "3_3") (pintype "passive"))
      (node (ref "R35") (pin "1") (pinfunction "1_1") (pintype "passive"))
      (node (ref "R40") (pin "1") (pinfunction "1_1") (pintype "passive"))
      (node (ref "U21") (pin "2") (pinfunction "A_2") (pintype "passive"))
    )
    (net (code "52") (name "PO_GND") (class "Default")
      (node (ref "J9") (pin "4") (pinfunction "4_4") (pintype "passive"))
      (node (ref "U16") (pin "3") (pinfunction "Em_3") (pintype "passive"))
      (node (ref "U17") (pin "3") (pinfunction "Em_3") (pintype "passive"))
      (node (ref "U22") (pin "3") (pinfunction "3_3") (pintype "passive"))
    )
    (net (code "53") (name "SHOOT") (class "Default")
      (node (ref "R29") (pin "2") (pinfunction "2_2") (pintype "passive"))
      (node (ref "U18") (pin "2") (pinfunction "B_2") (pintype "passive"))
    )
    (net (code "54") (name "SHOOT_OFF") (class "Default")
      (node (ref "R34") (pin "2") (pinfunction "2_2") (pintype "passive"))
      (node (ref "R38") (pin "1") (pinfunction "1_1") (pintype "passive"))
      (node (ref "U20") (pin "4") (pinfunction "OUT_4") (pintype "passive"))
    )
    (net (code "55") (name "SHTOOT_2") (class "Default")
      (node (ref "R26") (pin "2") (pinfunction "2_2") (pintype "passive"))
      (node (ref "U18") (pin "4") (pinfunction "Y_4") (pintype "passive"))
      (node (ref "U19") (pin "2") (pinfunction "INPUTA_2") (pintype "passive"))
    )
    (net (code "56") (name "SW_CLK") (class "Default")
      (node (ref "U11") (pin "2") (pinfunction "CLK_2") (pintype "passive"))
      (node (ref "U13") (pin "2") (pinfunction "CLK_2") (pintype "passive"))
    )
    (net (code "57") (name "SW_D") (class "Default")
      (node (ref "U11") (pin "9") (pinfunction "QH_9") (pintype "passive"))
    )
    (net (code "58") (name "SW_LD") (class "Default")
      (node (ref "U11") (pin "1") (pinfunction "SH/LD#_1") (pintype "passive"))
      (node (ref "U13") (pin "1") (pinfunction "SH/LD#_1") (pintype "passive"))
    )
    (net (code "59") (name "VBAT") (class "Default")
      (node (ref "C35") (pin "1") (pinfunction "1_1") (pintype "passive"))
      (node (ref "C36") (pin "1") (pinfunction "1_1") (pintype "passive"))
      (node (ref "C37") (pin "1") (pinfunction "1_1") (pintype "passive"))
      (node (ref "C47") (pin "1") (pinfunction "1_1") (pintype "passive"))
      (node (ref "D1") (pin "2") (pinfunction "K_2") (pintype "passive"))
      (node (ref "J4") (pin "2") (pinfunction "2_2") (pintype "passive"))
      (node (ref "J4") (pin "4") (pinfunction "4_4") (pintype "passive"))
      (node (ref "J4") (pin "6") (pinfunction "6_6") (pintype "passive"))
      (node (ref "J4") (pin "8") (pinfunction "8_8") (pintype "passive"))
      (node (ref "U19") (pin "6") (pinfunction "VCC_6") (pintype "passive"))
      (node (ref "U9") (pin "7") (pinfunction "VIN_7") (pintype "passive"))
    )
    (net (code "60") (name "unconnected-(J9-Pad5)") (class "Default")
      (node (ref "J9") (pin "5") (pinfunction "5_5") (pintype "passive+no_connect"))
    )
    (net (code "61") (name "unconnected-(U9-ENA-Pad5)") (class "Default")
      (node (ref "U9") (pin "5") (pinfunction "ENA_5") (pintype "passive+no_connect"))
    )
    (net (code "62") (name "unconnected-(U9-NC-Pad2)") (class "Default")
      (node (ref "U9") (pin "2") (pinfunction "NC_2") (pintype "passive+no_connect"))
    )
    (net (code "63") (name "unconnected-(U9-NC-Pad3)") (class "Default")
      (node (ref "U9") (pin "3") (pinfunction "NC_3") (pintype "passive+no_connect"))
    )
    (net (code "64") (name "unconnected-(U11-Q#H-Pad7)") (class "Default")
      (node (ref "U11") (pin "7") (pinfunction "Q#H_7") (pintype "passive+no_connect"))
    )
    (net (code "65") (name "unconnected-(U13-Q#H-Pad7)") (class "Default")
      (node (ref "U13") (pin "7") (pinfunction "Q#H_7") (pintype "passive+no_connect"))
    )
    (net (code "66") (name "unconnected-(U19-NC-Pad1)") (class "Default")
      (node (ref "U19") (pin "1") (pinfunction "NC_1") (pintype "passive+no_connect"))
    )
    (net (code "67") (name "unconnected-(U19-NC-Pad8)") (class "Default")
      (node (ref "U19") (pin "8") (pinfunction "NC_8") (pintype "passive+no_connect"))
    )
    (net (code "68") (name "unconnected-(U21-NC-Pad1)") (class "Default")
      (node (ref "U21") (pin "1") (pinfunction "NC_1") (pintype "passive+no_connect"))
    )
  )
)
